# PrototypeBoardV2A.net
KiCad netlist of a schematic drawn in EasyEDA Pro
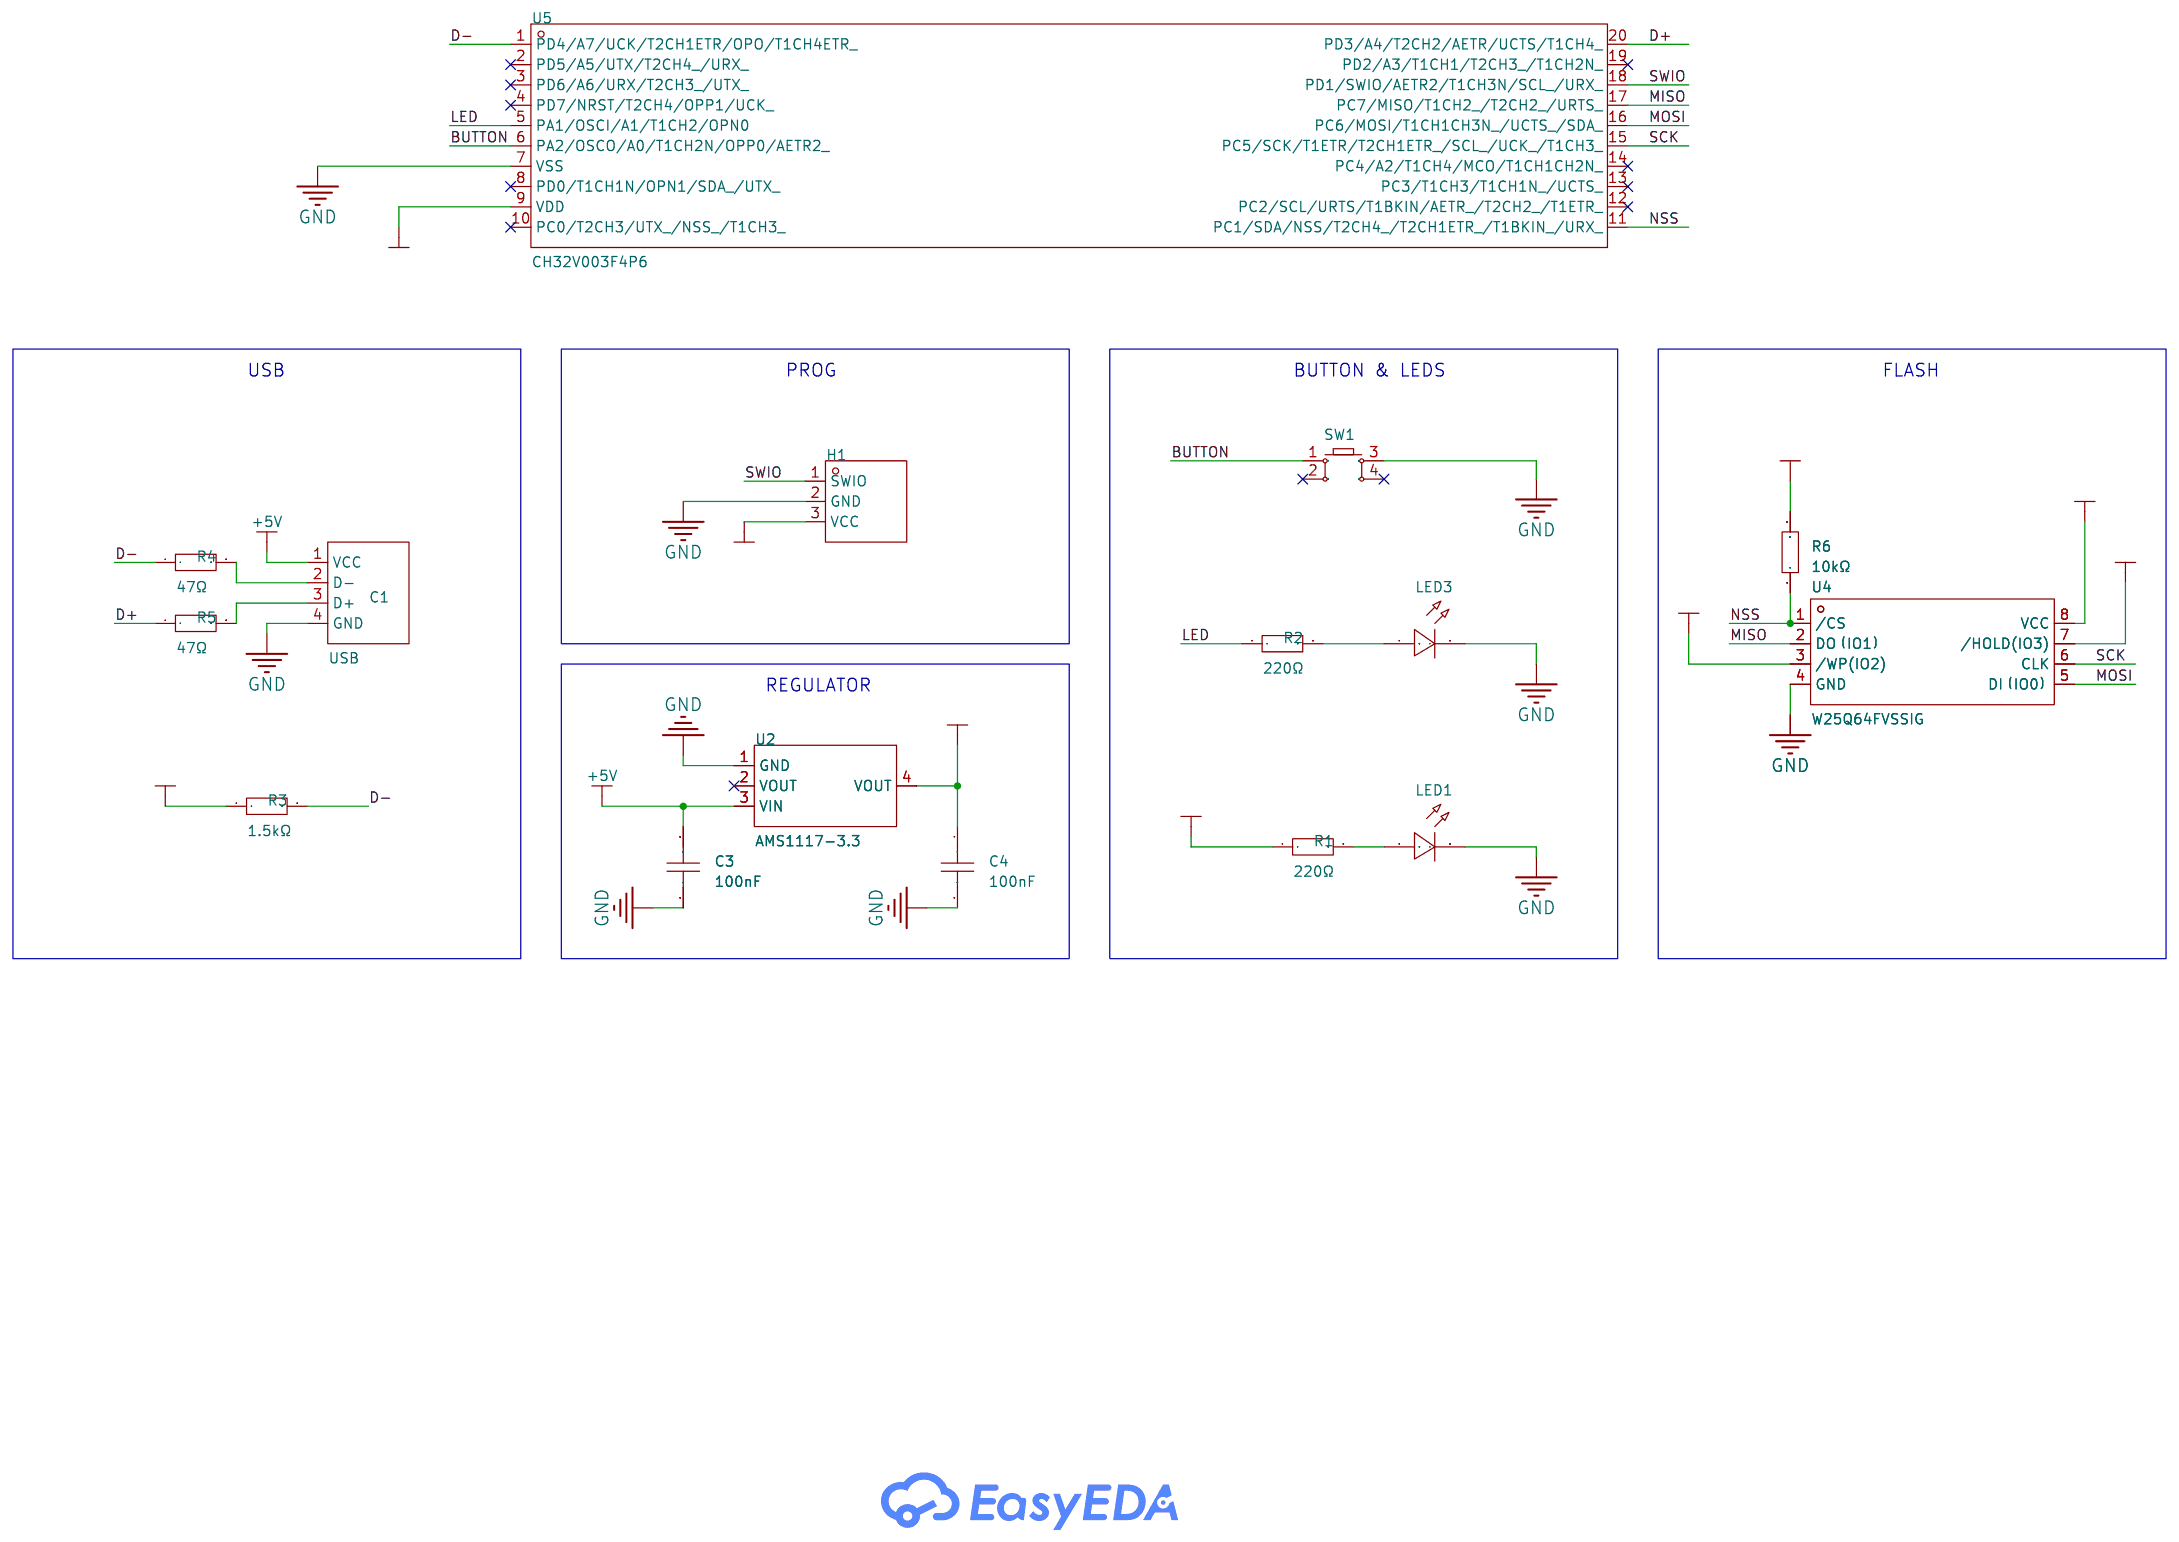
[diagram p0: schematic sheet]

(export (version "E")
  (design (tool "Eeschema 10.0.6"))
  (components
    (comp (ref "C1")
      (value "USB")
      (footprint "easyedapro:USB Type-C 4P")
      (libsource (lib "easyedapro") (part "USB Type-C 4P Board"))
    )
    (comp (ref "C3")
      (value "100nF")
      (footprint "easyedapro:CAP-TH_L5.8-W3.0-P4.7-D0.45")
      (fields (field (name "Manufacturer Part") "1C10Z5U104M050B") (field (name "Manufacturer") "VISHAY(威世)"))
      (libsource (lib "easyedapro") (part "1C10Z5U104M050B"))
    )
    (comp (ref "C4")
      (value "100nF")
      (footprint "easyedapro:CAP-TH_L5.8-W3.0-P4.7-D0.45")
      (fields (field (name "Manufacturer Part") "1C10Z5U104M050B") (field (name "Manufacturer") "VISHAY(威世)"))
      (libsource (lib "easyedapro") (part "1C10Z5U104M050B"))
    )
    (comp (ref "H1")
      (value "~")
      (footprint "easyedapro:HDR-TH_3P-P2.54-V-M")
      (libsource (lib "easyedapro") (part "PZ254V-11-03P_C2937625"))
    )
    (comp (ref "LED1")
      (value "~")
      (footprint "easyedapro:LED-TH_BD3.0-P2.54-FD")
      (libsource (lib "easyedapro") (part "LED_TH-R"))
    )
    (comp (ref "LED3")
      (value "~")
      (footprint "easyedapro:LED-TH_BD5.0-P2.54-L-RD_WHITE")
      (libsource (lib "easyedapro") (part "LED_TH-B"))
    )
    (comp (ref "R1")
      (value "220Ω")
      (footprint "easyedapro:RES-TH_BD1.8-L3.2-P7.20-D0.4")
      (libsource (lib "easyedapro") (part "Res"))
    )
    (comp (ref "R2")
      (value "220Ω")
      (footprint "easyedapro:RES-TH_BD1.8-L3.2-P7.20-D0.4")
      (libsource (lib "easyedapro") (part "Res"))
    )
    (comp (ref "R3")
      (value "1.5kΩ")
      (footprint "easyedapro:RES-TH_BD1.8-L3.2-P7.20-D0.4")
      (libsource (lib "easyedapro") (part "Res"))
    )
    (comp (ref "R4")
      (value "47Ω")
      (footprint "easyedapro:RES-TH_BD1.8-L3.2-P7.20-D0.4")
      (libsource (lib "easyedapro") (part "Res"))
    )
    (comp (ref "R5")
      (value "47Ω")
      (footprint "easyedapro:RES-TH_BD1.8-L3.2-P7.20-D0.4")
      (libsource (lib "easyedapro") (part "Res"))
    )
    (comp (ref "R6")
      (value "10kΩ")
      (footprint "easyedapro:RES-TH_BD1.8-L3.2-P7.20-D0.4")
      (libsource (lib "easyedapro") (part "Res"))
    )
    (comp (ref "SW1")
      (value "~")
      (footprint "easyedapro:KEY-TH_4P-L6.0-W6.0-P3.90-LS6.5")
      (libsource (lib "easyedapro") (part "轻触按键"))
    )
    (comp (ref "U2")
      (value "AMS1117-3.3")
      (footprint "easyedapro:SOT-223-3_L6.5-W3.4-P2.30-LS7.0-BR")
      (fields (field (name "Manufacturer") "AMS"))
      (libsource (lib "easyedapro") (part "AMS1117-3.3"))
    )
    (comp (ref "U4")
      (value "W25Q64FVSSIG")
      (footprint "easyedapro:SOIC-8_L5.3-W5.3-P1.27-LS8.0-BL")
      (libsource (lib "easyedapro") (part "W25Q64FVSSIG_C66141"))
    )
    (comp (ref "U5")
      (value "CH32V003F4P6")
      (footprint "easyedapro:TSSOP-20_L6.5-W4.4-P0.65-LS6.4-BL")
      (fields (field (name "Manufacturer") "WCH(南京沁恒)"))
      (libsource (lib "easyedapro") (part "CH32V003F4P6"))
    )
  )
  (nets
    (net (code "1") (name "+3.3V") (class "Default")
      (node (ref "C4") (pin "1") (pinfunction "1_1") (pintype "unspecified"))
      (node (ref "H1") (pin "3") (pinfunction "VCC_3") (pintype "unspecified"))
      (node (ref "R1") (pin "1") (pinfunction "1_1") (pintype "input"))
      (node (ref "R3") (pin "1") (pinfunction "1_1") (pintype "input"))
      (node (ref "R6") (pin "2") (pinfunction "2_2") (pintype "input"))
      (node (ref "U2") (pin "4") (pinfunction "VOUT_4") (pintype "unspecified"))
      (node (ref "U4") (pin "3") (pinfunction "/WP(IO2)_3") (pintype "unspecified"))
      (node (ref "U4") (pin "7") (pinfunction "/HOLD(IO3)_7") (pintype "unspecified"))
      (node (ref "U4") (pin "8") (pinfunction "VCC_8") (pintype "unspecified"))
      (node (ref "U5") (pin "9") (pinfunction "VDD_9") (pintype "unspecified"))
    )
    (net (code "2") (name "+5V") (class "Default")
      (node (ref "C1") (pin "1") (pinfunction "VCC_1") (pintype "input"))
      (node (ref "C3") (pin "2") (pinfunction "2_2") (pintype "unspecified"))
      (node (ref "U2") (pin "3") (pinfunction "VIN_3") (pintype "unspecified"))
    )
    (net (code "3") (name "/BUTTON") (class "Default")
      (node (ref "SW1") (pin "1") (pinfunction "1_1") (pintype "input"))
      (node (ref "U5") (pin "6") (pinfunction "PA2/OSCO/A0/T1CH2N/OPP0/AETR2__6") (pintype "unspecified"))
    )
    (net (code "4") (name "/D+") (class "Default")
      (node (ref "R5") (pin "1") (pinfunction "1_1") (pintype "input"))
      (node (ref "U5") (pin "20") (pinfunction "PD3/A4/T2CH2/AETR/UCTS/T1CH4__20") (pintype "unspecified"))
    )
    (net (code "5") (name "/D-") (class "Default")
      (node (ref "R3") (pin "2") (pinfunction "2_2") (pintype "input"))
      (node (ref "R4") (pin "1") (pinfunction "1_1") (pintype "input"))
      (node (ref "U5") (pin "1") (pinfunction "PD4/A7/UCK/T2CH1ETR/OPO/T1CH4ETR__1") (pintype "unspecified"))
    )
    (net (code "6") (name "/LED") (class "Default")
      (node (ref "R2") (pin "1") (pinfunction "1_1") (pintype "input"))
      (node (ref "U5") (pin "5") (pinfunction "PA1/OSCI/A1/T1CH2/OPN0_5") (pintype "unspecified"))
    )
    (net (code "7") (name "/MISO") (class "Default")
      (node (ref "U4") (pin "2") (pinfunction "DO（IO1）_2") (pintype "unspecified"))
      (node (ref "U5") (pin "17") (pinfunction "PC7/MISO/T1CH2_/T2CH2_/URTS__17") (pintype "unspecified"))
    )
    (net (code "8") (name "/MOSI") (class "Default")
      (node (ref "U4") (pin "5") (pinfunction "DI（IO0）_5") (pintype "unspecified"))
      (node (ref "U5") (pin "16") (pinfunction "PC6/MOSI/T1CH1CH3N_/UCTS_/SDA__16") (pintype "unspecified"))
    )
    (net (code "9") (name "/NSS") (class "Default")
      (node (ref "R6") (pin "1") (pinfunction "1_1") (pintype "input"))
      (node (ref "U4") (pin "1") (pinfunction "/CS_1") (pintype "unspecified"))
      (node (ref "U5") (pin "11") (pinfunction "PC1/SDA/NSS/T2CH4_/T2CH1ETR_/T1BKIN_/URX__11") (pintype "unspecified"))
    )
    (net (code "10") (name "/SCK") (class "Default")
      (node (ref "U4") (pin "6") (pinfunction "CLK_6") (pintype "unspecified"))
      (node (ref "U5") (pin "15") (pinfunction "PC5/SCK/T1ETR/T2CH1ETR_/SCL_/UCK_/T1CH3__15") (pintype "unspecified"))
    )
    (net (code "11") (name "/SWIO") (class "Default")
      (node (ref "H1") (pin "1") (pinfunction "SWIO_1") (pintype "unspecified"))
      (node (ref "U5") (pin "18") (pinfunction "PD1/SWIO/AETR2/T1CH3N/SCL_/URX__18") (pintype "unspecified"))
    )
    (net (code "12") (name "GND") (class "Default")
      (node (ref "C1") (pin "4") (pinfunction "GND_4") (pintype "input"))
      (node (ref "C3") (pin "1") (pinfunction "1_1") (pintype "unspecified"))
      (node (ref "C4") (pin "2") (pinfunction "2_2") (pintype "unspecified"))
      (node (ref "H1") (pin "2") (pinfunction "GND_2") (pintype "unspecified"))
      (node (ref "LED1") (pin "2") (pinfunction "A_2") (pintype "input"))
      (node (ref "LED3") (pin "2") (pinfunction "A_2") (pintype "input"))
      (node (ref "SW1") (pin "3") (pinfunction "3_3") (pintype "input"))
      (node (ref "U2") (pin "1") (pinfunction "GND_1") (pintype "unspecified"))
      (node (ref "U4") (pin "4") (pinfunction "GND_4") (pintype "unspecified"))
      (node (ref "U5") (pin "7") (pinfunction "VSS_7") (pintype "unspecified"))
    )
    (net (code "13") (name "Net-(C1-D+)") (class "Default")
      (node (ref "C1") (pin "3") (pinfunction "D+_3") (pintype "input"))
      (node (ref "R5") (pin "2") (pinfunction "2_2") (pintype "input"))
    )
    (net (code "14") (name "Net-(C1-D-)") (class "Default")
      (node (ref "C1") (pin "2") (pinfunction "D-_2") (pintype "input"))
      (node (ref "R4") (pin "2") (pinfunction "2_2") (pintype "input"))
    )
    (net (code "15") (name "Net-(LED1-C)") (class "Default")
      (node (ref "LED1") (pin "1") (pinfunction "C_1") (pintype "input"))
      (node (ref "R1") (pin "2") (pinfunction "2_2") (pintype "input"))
    )
    (net (code "16") (name "Net-(LED3-C)") (class "Default")
      (node (ref "LED3") (pin "1") (pinfunction "C_1") (pintype "input"))
      (node (ref "R2") (pin "2") (pinfunction "2_2") (pintype "input"))
    )
    (net (code "17") (name "unconnected-(SW1-Pad2)") (class "Default")
      (node (ref "SW1") (pin "2") (pinfunction "2_2") (pintype "input+no_connect"))
    )
    (net (code "18") (name "unconnected-(SW1-Pad4)") (class "Default")
      (node (ref "SW1") (pin "4") (pinfunction "4_4") (pintype "input+no_connect"))
    )
    (net (code "19") (name "unconnected-(U2-VOUT-Pad2)") (class "Default")
      (node (ref "U2") (pin "2") (pinfunction "VOUT_2") (pintype "unspecified+no_connect"))
    )
    (net (code "20") (name "unconnected-(U5-PC0{slash}T2CH3{slash}UTX_{slash}NSS_{slash}T1CH3_-Pad10)") (class "Default")
      (node (ref "U5") (pin "10") (pinfunction "PC0/T2CH3/UTX_/NSS_/T1CH3__10") (pintype "unspecified+no_connect"))
    )
    (net (code "21") (name "unconnected-(U5-PC2{slash}SCL{slash}URTS{slash}T1BKIN{slash}AETR_{slash}T2CH2_{slash}T1ETR_-Pad12)") (class "Default")
      (node (ref "U5") (pin "12") (pinfunction "PC2/SCL/URTS/T1BKIN/AETR_/T2CH2_/T1ETR__12") (pintype "unspecified+no_connect"))
    )
    (net (code "22") (name "unconnected-(U5-PC3{slash}T1CH3{slash}T1CH1N_{slash}UCTS_-Pad13)") (class "Default")
      (node (ref "U5") (pin "13") (pinfunction "PC3/T1CH3/T1CH1N_/UCTS__13") (pintype "unspecified+no_connect"))
    )
    (net (code "23") (name "unconnected-(U5-PC4{slash}A2{slash}T1CH4{slash}MCO{slash}T1CH1CH2N_-Pad14)") (class "Default")
      (node (ref "U5") (pin "14") (pinfunction "PC4/A2/T1CH4/MCO/T1CH1CH2N__14") (pintype "unspecified+no_connect"))
    )
    (net (code "24") (name "unconnected-(U5-PD0{slash}T1CH1N{slash}OPN1{slash}SDA_{slash}UTX_-Pad8)") (class "Default")
      (node (ref "U5") (pin "8") (pinfunction "PD0/T1CH1N/OPN1/SDA_/UTX__8") (pintype "unspecified+no_connect"))
    )
    (net (code "25") (name "unconnected-(U5-PD2{slash}A3{slash}T1CH1{slash}T2CH3_{slash}T1CH2N_-Pad19)") (class "Default")
      (node (ref "U5") (pin "19") (pinfunction "PD2/A3/T1CH1/T2CH3_/T1CH2N__19") (pintype "unspecified+no_connect"))
    )
    (net (code "26") (name "unconnected-(U5-PD5{slash}A5{slash}UTX{slash}T2CH4_{slash}URX_-Pad2)") (class "Default")
      (node (ref "U5") (pin "2") (pinfunction "PD5/A5/UTX/T2CH4_/URX__2") (pintype "unspecified+no_connect"))
    )
    (net (code "27") (name "unconnected-(U5-PD6{slash}A6{slash}URX{slash}T2CH3_{slash}UTX_-Pad3)") (class "Default")
      (node (ref "U5") (pin "3") (pinfunction "PD6/A6/URX/T2CH3_/UTX__3") (pintype "unspecified+no_connect"))
    )
    (net (code "28") (name "unconnected-(U5-PD7{slash}NRST{slash}T2CH4{slash}OPP1{slash}UCK_-Pad4)") (class "Default")
      (node (ref "U5") (pin "4") (pinfunction "PD7/NRST/T2CH4/OPP1/UCK__4") (pintype "unspecified+no_connect"))
    )
  )
)
